# MCU.net
KiCad netlist of a schematic drawn in Altium Designer
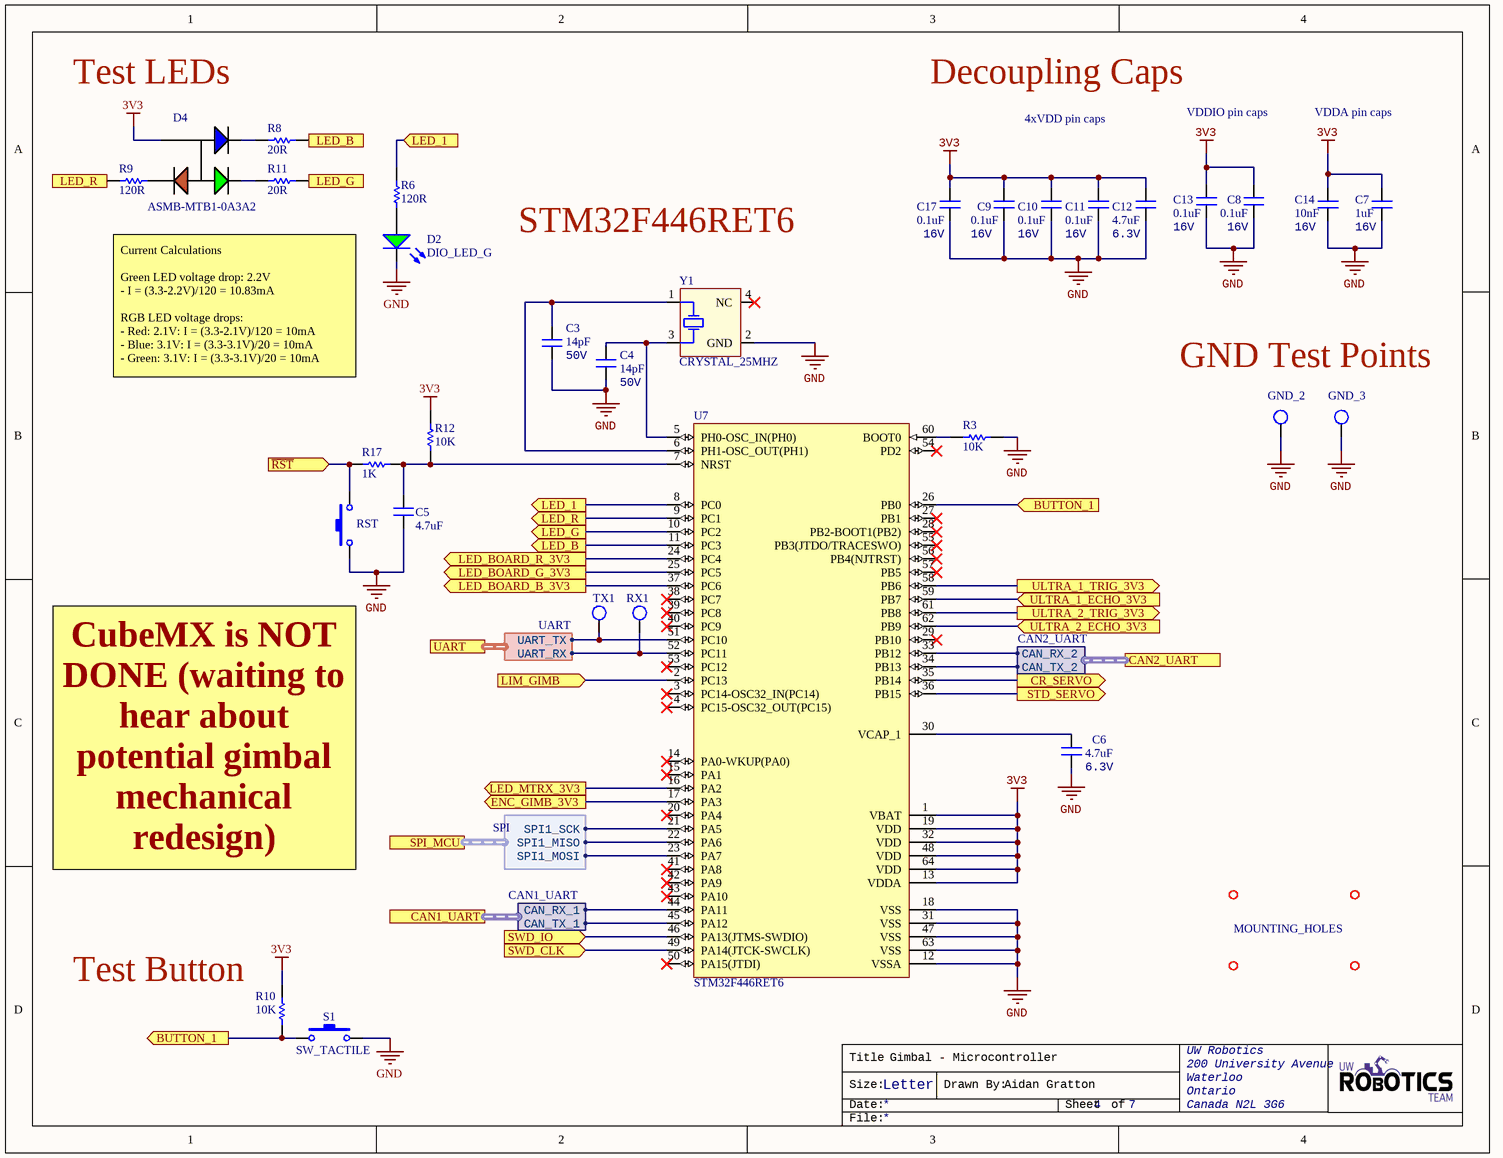
[diagram p0: MCU.SchDoc]

(export (version "E")
  (design (tool "Eeschema 10.0.6"))
  (components
    (comp (ref "C3")
      (value "14pF")
      (footprint "CAPC0603(1608)55_N")
      (description "Cap Ceramic 14pF 50V C0G 5% SMD 0603 125C Cardboard T/R")
      (fields
        (field (name "TOLERANCE") "5%")
        (field (name "VOLTAGE RATING (DC)") "50V")
        (field (name "Comment") "CL10C140JB8NNNC")
      )
      (libsource (lib "UWRT_Schematic_Library_2020") (part "CL10C140JB8NNNC"))
    )
    (comp (ref "C4")
      (value "14pF")
      (footprint "CAPC0603(1608)55_N")
      (description "Cap Ceramic 14pF 50V C0G 5% SMD 0603 125C Cardboard T/R")
      (fields
        (field (name "TOLERANCE") "5%")
        (field (name "VOLTAGE RATING (DC)") "50V")
        (field (name "Comment") "CL10C140JB8NNNC")
      )
      (libsource (lib "UWRT_Schematic_Library_2020") (part "CL10C140JB8NNNC"))
    )
    (comp (ref "C5")
      (value "4.7uF")
      (footprint "CAPC0603(1608)55_N")
      (description "CAP CER 4.7UF 6.3V X5R 0603")
      (fields (field (name "Comment") "CAP_4.7uF_0603"))
      (libsource (lib "UWRT_Schematic_Library_2020") (part "CAP_4.7uF_0603"))
    )
    (comp (ref "C6")
      (value "4.7uF")
      (footprint "CAPC0603(1608)55_N")
      (description "CAP CER 4.7UF 6.3V X5R 0603")
      (fields
        (field (name "MANUFACTURER") "Yageo")
        (field (name "VOLTAGE RATING") "6.3V")
        (field (name "MPN") "CC0603KRX5R5BB475")
      )
      (libsource (lib "UWRT_Schematic_Library_2020") (part "CAP_4.7uF_0603"))
    )
    (comp (ref "C7")
      (value "1uF")
      (footprint "CAPC0603(1608)55_N")
      (description "CAP CER 1UF 16V Y5V 0603")
      (fields
        (field (name "MANUFACTURER") "Yageo")
        (field (name "VOLTAGE RATING") "16V")
        (field (name "MPN") "CC0603ZRY5V7BB105")
      )
      (libsource (lib "UWRT_Schematic_Library_2020") (part "CAP_1uF_16V_0603"))
    )
    (comp (ref "C8")
      (value "0.1uF")
      (footprint "CAPC0603(1608)55_N")
      (description "CAP CER 0.1UF 16V X7R 0603")
      (fields
        (field (name "MANUFACTURER") "Yageo")
        (field (name "VOLTAGE RATING") "16V")
        (field (name "MPN") "CC0603KRX7R7BB104")
      )
      (libsource (lib "UWRT_Schematic_Library_2020") (part "CAP_0.1uF_16V_0603"))
    )
    (comp (ref "C9")
      (value "0.1uF")
      (footprint "CAPC0603(1608)55_N")
      (description "CAP CER 0.1UF 16V X7R 0603")
      (fields
        (field (name "MANUFACTURER") "Yageo")
        (field (name "VOLTAGE RATING") "16V")
        (field (name "MPN") "CC0603KRX7R7BB104")
      )
      (libsource (lib "UWRT_Schematic_Library_2020") (part "CAP_0.1uF_16V_0603"))
    )
    (comp (ref "C10")
      (value "0.1uF")
      (footprint "CAPC0603(1608)55_N")
      (description "CAP CER 0.1UF 16V X7R 0603")
      (fields
        (field (name "MANUFACTURER") "Yageo")
        (field (name "VOLTAGE RATING") "16V")
        (field (name "MPN") "CC0603KRX7R7BB104")
      )
      (libsource (lib "UWRT_Schematic_Library_2020") (part "CAP_0.1uF_16V_0603"))
    )
    (comp (ref "C11")
      (value "0.1uF")
      (footprint "CAPC0603(1608)55_N")
      (description "CAP CER 0.1UF 16V X7R 0603")
      (fields
        (field (name "MANUFACTURER") "Yageo")
        (field (name "VOLTAGE RATING") "16V")
        (field (name "MPN") "CC0603KRX7R7BB104")
      )
      (libsource (lib "UWRT_Schematic_Library_2020") (part "CAP_0.1uF_16V_0603"))
    )
    (comp (ref "C12")
      (value "4.7uF")
      (footprint "CAPC0603(1608)55_N")
      (description "CAP CER 4.7UF 6.3V X5R 0603")
      (fields
        (field (name "MANUFACTURER") "Yageo")
        (field (name "VOLTAGE RATING") "6.3V")
        (field (name "MPN") "CC0603KRX5R5BB475")
      )
      (libsource (lib "UWRT_Schematic_Library_2020") (part "CAP_4.7uF_0603"))
    )
    (comp (ref "C13")
      (value "0.1uF")
      (footprint "CAPC0603(1608)55_N")
      (description "CAP CER 0.1UF 16V X7R 0603")
      (fields
        (field (name "MANUFACTURER") "Yageo")
        (field (name "VOLTAGE RATING") "16V")
        (field (name "MPN") "CC0603KRX7R7BB104")
      )
      (libsource (lib "UWRT_Schematic_Library_2020") (part "CAP_0.1uF_16V_0603"))
    )
    (comp (ref "C14")
      (value "10nF")
      (footprint "CAPC0603(1608)55_N")
      (description "CAP CER 10000PF 16V X7R 0603")
      (fields
        (field (name "MANUFACTURER") "Yageo")
        (field (name "VOLTAGE RATING") "16V")
        (field (name "MPN") "CC0603KRX7R7BB103")
      )
      (libsource (lib "UWRT_Schematic_Library_2020") (part "CAP_10nF_0603"))
    )
    (comp (ref "C17")
      (value "0.1uF")
      (footprint "CAPC0603(1608)55_N")
      (description "CAP CER 0.1UF 16V X7R 0603")
      (fields
        (field (name "MANUFACTURER") "Yageo")
        (field (name "VOLTAGE RATING") "16V")
        (field (name "MPN") "CC0603KRX7R7BB104")
      )
      (libsource (lib "UWRT_Schematic_Library_2020") (part "CAP_0.1uF_16V_0603"))
    )
    (comp (ref "D2")
      (value "DIO_LED_G")
      (footprint "LED_0805_LINE")
      (description "LED GREEN DIFFUSED 0805 SMD")
      (fields (field (name "MANUFACTURER") "OSRAM") (field (name "MPN") "LG R971-KN-1"))
      (libsource (lib "UWRT_Schematic_Library_2020") (part "DIO_LED_G"))
    )
    (comp (ref "D4")
      (value "LED_RGB")
      (footprint "LED_RGB")
      (description "LED RGB DIFFUSED 4PLCC SMD")
      (fields (field (name "MANUFACTURER PART NUMBER 1") "ASMB-MTB1-0A3A2"))
      (libsource (lib "UWRT_Schematic_Library_2020") (part "LED_RGB"))
    )
    (comp (ref "GND_2")
      (value "TESTPOINT_LOOP")
      (footprint "TESTPOINT_LOOP")
      (description "Loop testpoint through-hole pad")
      (fields (field (name "MANUFACTURER") "Keystone Electronics"))
      (libsource (lib "UWRT_Schematic_Library_2020") (part "TESTPOINT_LOOP"))
    )
    (comp (ref "GND_3")
      (value "TESTPOINT_LOOP")
      (footprint "TESTPOINT_LOOP")
      (description "Loop testpoint through-hole pad")
      (fields (field (name "MANUFACTURER") "Keystone Electronics"))
      (libsource (lib "UWRT_Schematic_Library_2020") (part "TESTPOINT_LOOP"))
    )
    (comp (ref "MH1")
      (value "MOUNTING_HOLES")
      (footprint "MOUNTING_HOLE")
      (description "6cm x 6cm")
      (libsource (lib "UWRT_Schematic_Library_2020") (part "MOUNTING_HOLES"))
    )
    (comp (ref "MH2")
      (value "MOUNTING_HOLES")
      (footprint "MOUNTING_HOLE")
      (description "6cm x 6cm")
      (libsource (lib "UWRT_Schematic_Library_2020") (part "MOUNTING_HOLES"))
    )
    (comp (ref "MH3")
      (value "MOUNTING_HOLES")
      (footprint "MOUNTING_HOLE")
      (description "6cm x 6cm")
      (libsource (lib "UWRT_Schematic_Library_2020") (part "MOUNTING_HOLES"))
    )
    (comp (ref "MH4")
      (value "MOUNTING_HOLES")
      (footprint "MOUNTING_HOLE")
      (description "6cm x 6cm")
      (libsource (lib "UWRT_Schematic_Library_2020") (part "MOUNTING_HOLES"))
    )
    (comp (ref "R3")
      (value "10K")
      (footprint "RESC0603(1608)_N")
      (description "RES SMD 10K OHM 5% 1/10W 0603")
      (fields (field (name "MANUFACTURER") "Yageo") (field (name "MPN") "RC0603JR-0710KL"))
      (libsource (lib "UWRT_Schematic_Library_2020") (part "RES_10K_0603"))
    )
    (comp (ref "R6")
      (value "120R")
      (footprint "RESC0603(1608)_N")
      (description "RES SMD 120 OHM 5% 1/10W 0603")
      (fields (field (name "MANUFACTURER") "Yageo") (field (name "MPN") "RC0603JR-07120RL"))
      (libsource (lib "UWRT_Schematic_Library_2020") (part "RES_120R_0603"))
    )
    (comp (ref "R8")
      (value "20R")
      (footprint "RESC0603(1608)_N")
      (description "RES SMD 20 OHM 5% 1/10W 0603")
      (fields (field (name "MANUFACTURER") "Yageo") (field (name "MPN") "RC0603JR-0720RL"))
      (libsource (lib "UWRT_Schematic_Library_2020") (part "RES_20R_0603"))
    )
    (comp (ref "R9")
      (value "120R")
      (footprint "RESC0603(1608)_N")
      (description "RES SMD 120 OHM 5% 1/10W 0603")
      (fields (field (name "MANUFACTURER") "Yageo") (field (name "MPN") "RC0603JR-07120RL"))
      (libsource (lib "UWRT_Schematic_Library_2020") (part "RES_120R_0603"))
    )
    (comp (ref "R10")
      (value "10K")
      (footprint "RESC0603(1608)_N")
      (description "RES SMD 10K OHM 5% 1/10W 0603")
      (fields (field (name "MANUFACTURER") "Yageo") (field (name "TOLERANCE") "5%"))
      (libsource (lib "UWRT_Schematic_Library_2020") (part "RES_10K_0603"))
    )
    (comp (ref "R11")
      (value "20R")
      (footprint "RESC0603(1608)_N")
      (description "RES SMD 20 OHM 5% 1/10W 0603")
      (fields (field (name "MANUFACTURER") "Yageo") (field (name "MPN") "RC0603JR-0720RL"))
      (libsource (lib "UWRT_Schematic_Library_2020") (part "RES_20R_0603"))
    )
    (comp (ref "R12")
      (value "10K")
      (footprint "RESC0603(1608)_N")
      (description "RES SMD 10K OHM 5% 1/10W 0603")
      (fields (field (name "MANUFACTURER") "Yageo") (field (name "MPN") "RC0603JR-0710KL"))
      (libsource (lib "UWRT_Schematic_Library_2020") (part "RES_10K_0603"))
    )
    (comp (ref "R17")
      (value "1K")
      (footprint "RESC0603(1608)_N")
      (description "RES SMD 1K OHM 5% 1/10W 0603")
      (fields (field (name "TOLERANCE") "5%") (field (name "Comment") "RES_1K_0603"))
      (libsource (lib "UWRT_Schematic_Library_2020") (part "RES_1K_0603"))
    )
    (comp (ref "RST")
      (value "SW_PWR")
      (footprint "PTS830GM140")
      (description "Power Switch (Red)")
      (fields (field (name "MPN") "PTS830GM140 SMTR LFS") (field (name "MANUFACTURER") "C&K"))
      (libsource (lib "UWRT_Schematic_Library_2020") (part "SW_PWR"))
    )
    (comp (ref "RX1")
      (value "TESTPOINT_LOOP")
      (footprint "TESTPOINT_LOOP")
      (description "Loop testpoint through-hole pad")
      (fields (field (name "MANUFACTURER") "Keystone Electronics"))
      (libsource (lib "UWRT_Schematic_Library_2020") (part "TESTPOINT_LOOP"))
    )
    (comp (ref "S1")
      (value "SW_TACTILE")
      (footprint "B3U-1100P")
      (description "Tactile Switch (Grey)")
      (fields (field (name "MPN") "B3U-1100P") (field (name "MANUFACTURER") "Omron Electronics Inc-EMC Div"))
      (libsource (lib "UWRT_Schematic_Library_2020") (part "SW_TACTILE"))
    )
    (comp (ref "TX1")
      (value "TESTPOINT_LOOP")
      (footprint "TESTPOINT_LOOP")
      (description "Loop testpoint through-hole pad")
      (fields (field (name "MANUFACTURER") "Keystone Electronics"))
      (libsource (lib "UWRT_Schematic_Library_2020") (part "TESTPOINT_LOOP"))
    )
    (comp (ref "U7")
      (value "STM32F446RET6")
      (footprint "STM-LQFP64_L")
      (libsource (lib "UWRT_Schematic_Library_2020") (part "MCU_STM32F446RET6"))
    )
    (comp (ref "Y1")
      (value "CRYSTAL_25MHZ")
      (footprint "AVX-CX2520DB32000D0GEJZ1-4_V")
      (description "CRYSTAL 25.0000MHZ 12PF SMD")
      (libsource (lib "UWRT_Schematic_Library_2020") (part "CRYSTAL_25MHZ"))
    )
  )
  (nets
    (net (code "5") (name "/BUTTON_1") (class "Default")
      (node (ref "R10") (pin "2") (pinfunction "2_2") (pintype "passive"))
      (node (ref "S1") (pin "1") (pinfunction "1_1") (pintype "passive"))
      (node (ref "U7") (pin "26") (pinfunction "PB0_26") (pintype "bidirectional"))
    )
    (net (code "6") (name "/CAN_RX_1") (class "Default")
      (node (ref "U7") (pin "44") (pinfunction "PA11_44") (pintype "bidirectional"))
    )
    (net (code "7") (name "/CAN_RX_2") (class "Default")
      (node (ref "U7") (pin "33") (pinfunction "PB12_33") (pintype "bidirectional"))
    )
    (net (code "8") (name "/CAN_TX_1") (class "Default")
      (node (ref "U7") (pin "45") (pinfunction "PA12_45") (pintype "bidirectional"))
    )
    (net (code "9") (name "/CAN_TX_2") (class "Default")
      (node (ref "U7") (pin "34") (pinfunction "PB13_34") (pintype "bidirectional"))
    )
    (net (code "10") (name "/CR_SERVO") (class "Default")
      (node (ref "U7") (pin "35") (pinfunction "PB14_35") (pintype "bidirectional"))
    )
    (net (code "11") (name "/ENC_GIMB_3V3") (class "Default")
      (node (ref "U7") (pin "17") (pinfunction "PA3_17") (pintype "bidirectional"))
    )
    (net (code "12") (name "/LED_1") (class "Default")
      (node (ref "R6") (pin "1") (pinfunction "1_1") (pintype "passive"))
      (node (ref "U7") (pin "8") (pinfunction "PC0_8") (pintype "bidirectional"))
    )
    (net (code "13") (name "/LED_B") (class "Default")
      (node (ref "R8") (pin "2") (pinfunction "2_2") (pintype "passive"))
      (node (ref "U7") (pin "11") (pinfunction "PC3_11") (pintype "bidirectional"))
    )
    (net (code "14") (name "/LED_BOARD_B_3V3") (class "Default")
      (node (ref "U7") (pin "37") (pinfunction "PC6_37") (pintype "bidirectional"))
    )
    (net (code "15") (name "/LED_BOARD_G_3V3") (class "Default")
      (node (ref "U7") (pin "25") (pinfunction "PC5_25") (pintype "bidirectional"))
    )
    (net (code "16") (name "/LED_BOARD_R_3V3") (class "Default")
      (node (ref "U7") (pin "24") (pinfunction "PC4_24") (pintype "bidirectional"))
    )
    (net (code "17") (name "/LED_G") (class "Default")
      (node (ref "R11") (pin "2") (pinfunction "2_2") (pintype "passive"))
      (node (ref "U7") (pin "10") (pinfunction "PC2_10") (pintype "bidirectional"))
    )
    (net (code "18") (name "/LED_MTRX_3V3") (class "Default")
      (node (ref "U7") (pin "16") (pinfunction "PA2_16") (pintype "bidirectional"))
    )
    (net (code "19") (name "/LED_R") (class "Default")
      (node (ref "R9") (pin "1") (pinfunction "1_1") (pintype "passive"))
      (node (ref "U7") (pin "9") (pinfunction "PC1_9") (pintype "bidirectional"))
    )
    (net (code "20") (name "/LIM_GIMB") (class "Default")
      (node (ref "U7") (pin "2") (pinfunction "PC13_2") (pintype "bidirectional"))
    )
    (net (code "21") (name "/SPI1_MISO") (class "Default")
      (node (ref "U7") (pin "22") (pinfunction "PA6_22") (pintype "bidirectional"))
    )
    (net (code "22") (name "/SPI1_MOSI") (class "Default")
      (node (ref "U7") (pin "23") (pinfunction "PA7_23") (pintype "bidirectional"))
    )
    (net (code "23") (name "/SPI1_SCK") (class "Default")
      (node (ref "U7") (pin "21") (pinfunction "PA5_21") (pintype "bidirectional"))
    )
    (net (code "24") (name "/STD_SERVO") (class "Default")
      (node (ref "U7") (pin "36") (pinfunction "PB15_36") (pintype "bidirectional"))
    )
    (net (code "25") (name "/SWD_CLK") (class "Default")
      (node (ref "U7") (pin "49") (pinfunction "PA14(JTCK-SWCLK)_49") (pintype "bidirectional"))
    )
    (net (code "26") (name "/SWD_IO") (class "Default")
      (node (ref "U7") (pin "46") (pinfunction "PA13(JTMS-SWDIO)_46") (pintype "bidirectional"))
    )
    (net (code "27") (name "/UART_RX") (class "Default")
      (node (ref "RX1") (pin "1") (pintype "passive"))
      (node (ref "U7") (pin "52") (pinfunction "PC11_52") (pintype "bidirectional"))
    )
    (net (code "28") (name "/UART_TX") (class "Default")
      (node (ref "TX1") (pin "1") (pintype "passive"))
      (node (ref "U7") (pin "51") (pinfunction "PC10_51") (pintype "bidirectional"))
    )
    (net (code "29") (name "/ULTRA_1_ECHO_3V3") (class "Default")
      (node (ref "U7") (pin "59") (pinfunction "PB7_59") (pintype "bidirectional"))
    )
    (net (code "30") (name "/ULTRA_1_TRIG_3V3") (class "Default")
      (node (ref "U7") (pin "58") (pinfunction "PB6_58") (pintype "bidirectional"))
    )
    (net (code "31") (name "/ULTRA_2_ECHO_3V3") (class "Default")
      (node (ref "U7") (pin "62") (pinfunction "PB9_62") (pintype "bidirectional"))
    )
    (net (code "32") (name "/ULTRA_2_TRIG_3V3") (class "Default")
      (node (ref "U7") (pin "61") (pinfunction "PB8_61") (pintype "bidirectional"))
    )
    (net (code "37") (name "/~{RST}") (class "Default")
      (node (ref "R17") (pin "1") (pinfunction "1_1") (pintype "passive"))
      (node (ref "RST") (pin "2") (pinfunction "2_2") (pintype "passive"))
    )
    (net (code "38") (name "3V3") (class "Default")
      (node (ref "C10") (pin "2") (pinfunction "2_2") (pintype "passive"))
      (node (ref "C11") (pin "2") (pinfunction "2_2") (pintype "passive"))
      (node (ref "C12") (pin "2") (pinfunction "2_2") (pintype "passive"))
      (node (ref "C13") (pin "2") (pinfunction "2_2") (pintype "passive"))
      (node (ref "C14") (pin "2") (pinfunction "2_2") (pintype "passive"))
      (node (ref "C17") (pin "2") (pinfunction "2_2") (pintype "passive"))
      (node (ref "C7") (pin "2") (pinfunction "2_2") (pintype "passive"))
      (node (ref "C8") (pin "2") (pinfunction "2_2") (pintype "passive"))
      (node (ref "C9") (pin "2") (pinfunction "2_2") (pintype "passive"))
      (node (ref "D4") (pin "4") (pinfunction "9_4") (pintype "passive"))
      (node (ref "R10") (pin "1") (pinfunction "1_1") (pintype "passive"))
      (node (ref "R12") (pin "2") (pinfunction "2_2") (pintype "passive"))
      (node (ref "U7") (pin "1") (pinfunction "VBAT_1") (pintype "power_in"))
      (node (ref "U7") (pin "13") (pinfunction "VDDA_13") (pintype "power_in"))
      (node (ref "U7") (pin "19") (pinfunction "VDD_19") (pintype "power_in"))
      (node (ref "U7") (pin "32") (pinfunction "VDD_32") (pintype "power_in"))
      (node (ref "U7") (pin "48") (pinfunction "VDD_48") (pintype "power_in"))
      (node (ref "U7") (pin "64") (pinfunction "VDD_64") (pintype "power_in"))
    )
    (net (code "39") (name "GND") (class "Default")
      (node (ref "C10") (pin "1") (pinfunction "1_1") (pintype "passive"))
      (node (ref "C11") (pin "1") (pinfunction "1_1") (pintype "passive"))
      (node (ref "C12") (pin "1") (pinfunction "1_1") (pintype "passive"))
      (node (ref "C13") (pin "1") (pinfunction "1_1") (pintype "passive"))
      (node (ref "C14") (pin "1") (pinfunction "1_1") (pintype "passive"))
      (node (ref "C17") (pin "1") (pinfunction "1_1") (pintype "passive"))
      (node (ref "C3") (pin "1") (pinfunction "1_1") (pintype "passive"))
      (node (ref "C4") (pin "1") (pinfunction "1_1") (pintype "passive"))
      (node (ref "C5") (pin "1") (pinfunction "1_1") (pintype "passive"))
      (node (ref "C6") (pin "1") (pinfunction "1_1") (pintype "passive"))
      (node (ref "C7") (pin "1") (pinfunction "1_1") (pintype "passive"))
      (node (ref "C8") (pin "1") (pinfunction "1_1") (pintype "passive"))
      (node (ref "C9") (pin "1") (pinfunction "1_1") (pintype "passive"))
      (node (ref "D2") (pin "2") (pinfunction "K_2") (pintype "passive"))
      (node (ref "GND_2") (pin "1") (pintype "passive"))
      (node (ref "GND_3") (pin "1") (pintype "passive"))
      (node (ref "R3") (pin "2") (pinfunction "2_2") (pintype "passive"))
      (node (ref "RST") (pin "1") (pinfunction "1_1") (pintype "passive"))
      (node (ref "S1") (pin "2") (pinfunction "2_2") (pintype "passive"))
      (node (ref "U7") (pin "12") (pinfunction "VSSA_12") (pintype "power_in"))
      (node (ref "U7") (pin "18") (pinfunction "VSS_18") (pintype "power_in"))
      (node (ref "U7") (pin "31") (pinfunction "VSS_31") (pintype "power_in"))
      (node (ref "U7") (pin "47") (pinfunction "VSS_47") (pintype "power_in"))
      (node (ref "U7") (pin "63") (pinfunction "VSS_63") (pintype "power_in"))
      (node (ref "Y1") (pin "2") (pinfunction "GND_2") (pintype "power_in"))
    )
    (net (code "40") (name "Net-(D2-A)") (class "Default")
      (node (ref "D2") (pin "1") (pinfunction "A_1") (pintype "passive"))
      (node (ref "R6") (pin "2") (pinfunction "2_2") (pintype "passive"))
    )
    (net (code "41") (name "Net-(D4-10)") (class "Default")
      (node (ref "D4") (pin "3") (pinfunction "10_3") (pintype "passive"))
      (node (ref "R8") (pin "1") (pinfunction "1_1") (pintype "passive"))
    )
    (net (code "42") (name "Net-(D4-11)") (class "Default")
      (node (ref "D4") (pin "1") (pinfunction "11_1") (pintype "passive"))
      (node (ref "R9") (pin "2") (pinfunction "2_2") (pintype "passive"))
    )
    (net (code "43") (name "Net-(D4-12)") (class "Default")
      (node (ref "D4") (pin "2") (pinfunction "12_2") (pintype "passive"))
      (node (ref "R11") (pin "1") (pinfunction "1_1") (pintype "passive"))
    )
    (net (code "44") (name "Net-(U7-BOOT0)") (class "Default")
      (node (ref "R3") (pin "1") (pinfunction "1_1") (pintype "passive"))
      (node (ref "U7") (pin "60") (pinfunction "BOOT0_60") (pintype "input"))
    )
    (net (code "45") (name "Net-(U7-NRST)") (class "Default")
      (node (ref "C5") (pin "2") (pinfunction "2_2") (pintype "passive"))
      (node (ref "R12") (pin "1") (pinfunction "1_1") (pintype "passive"))
      (node (ref "R17") (pin "2") (pinfunction "2_2") (pintype "passive"))
      (node (ref "U7") (pin "7") (pinfunction "NRST_7") (pintype "bidirectional"))
    )
    (net (code "46") (name "Net-(U7-PH0-OSC_IN(PH0))") (class "Default")
      (node (ref "C4") (pin "2") (pinfunction "2_2") (pintype "passive"))
      (node (ref "U7") (pin "5") (pinfunction "PH0-OSC_IN(PH0)_5") (pintype "bidirectional"))
      (node (ref "Y1") (pin "3") (pinfunction "HOT_3") (pintype "passive"))
    )
    (net (code "47") (name "Net-(U7-PH1-OSC_OUT(PH1))") (class "Default")
      (node (ref "C3") (pin "2") (pinfunction "2_2") (pintype "passive"))
      (node (ref "U7") (pin "6") (pinfunction "PH1-OSC_OUT(PH1)_6") (pintype "bidirectional"))
      (node (ref "Y1") (pin "1") (pinfunction "HOT_1") (pintype "passive"))
    )
    (net (code "48") (name "Net-(U7-VCAP_1)") (class "Default")
      (node (ref "C6") (pin "2") (pinfunction "2_2") (pintype "passive"))
      (node (ref "U7") (pin "30") (pinfunction "VCAP_1_30") (pintype "passive"))
    )
    (net (code "49") (name "unconnected-(U7-PA0-WKUP(PA0)-Pad14)") (class "Default")
      (node (ref "U7") (pin "14") (pinfunction "PA0-WKUP(PA0)_14") (pintype "bidirectional+no_connect"))
    )
    (net (code "50") (name "unconnected-(U7-PA1-Pad15)") (class "Default")
      (node (ref "U7") (pin "15") (pinfunction "PA1_15") (pintype "bidirectional+no_connect"))
    )
    (net (code "51") (name "unconnected-(U7-PA4-Pad20)") (class "Default")
      (node (ref "U7") (pin "20") (pinfunction "PA4_20") (pintype "bidirectional+no_connect"))
    )
    (net (code "52") (name "unconnected-(U7-PA8-Pad41)") (class "Default")
      (node (ref "U7") (pin "41") (pinfunction "PA8_41") (pintype "bidirectional+no_connect"))
    )
    (net (code "53") (name "unconnected-(U7-PA9-Pad42)") (class "Default")
      (node (ref "U7") (pin "42") (pinfunction "PA9_42") (pintype "bidirectional+no_connect"))
    )
    (net (code "54") (name "unconnected-(U7-PA10-Pad43)") (class "Default")
      (node (ref "U7") (pin "43") (pinfunction "PA10_43") (pintype "bidirectional+no_connect"))
    )
    (net (code "55") (name "unconnected-(U7-PA15(JTDI)-Pad50)") (class "Default")
      (node (ref "U7") (pin "50") (pinfunction "PA15(JTDI)_50") (pintype "bidirectional+no_connect"))
    )
    (net (code "56") (name "unconnected-(U7-PB1-Pad27)") (class "Default")
      (node (ref "U7") (pin "27") (pinfunction "PB1_27") (pintype "bidirectional+no_connect"))
    )
    (net (code "57") (name "unconnected-(U7-PB2-BOOT1(PB2)-Pad28)") (class "Default")
      (node (ref "U7") (pin "28") (pinfunction "PB2-BOOT1(PB2)_28") (pintype "bidirectional+no_connect"))
    )
    (net (code "58") (name "unconnected-(U7-PB3(JTDO{slash}TRACESWO)-Pad55)") (class "Default")
      (node (ref "U7") (pin "55") (pinfunction "PB3(JTDO/TRACESWO)_55") (pintype "bidirectional+no_connect"))
    )
    (net (code "59") (name "unconnected-(U7-PB4(NJTRST)-Pad56)") (class "Default")
      (node (ref "U7") (pin "56") (pinfunction "PB4(NJTRST)_56") (pintype "bidirectional+no_connect"))
    )
    (net (code "60") (name "unconnected-(U7-PB5-Pad57)") (class "Default")
      (node (ref "U7") (pin "57") (pinfunction "PB5_57") (pintype "bidirectional+no_connect"))
    )
    (net (code "61") (name "unconnected-(U7-PB10-Pad29)") (class "Default")
      (node (ref "U7") (pin "29") (pinfunction "PB10_29") (pintype "bidirectional+no_connect"))
    )
    (net (code "62") (name "unconnected-(U7-PC7-Pad38)") (class "Default")
      (node (ref "U7") (pin "38") (pinfunction "PC7_38") (pintype "bidirectional+no_connect"))
    )
    (net (code "63") (name "unconnected-(U7-PC8-Pad39)") (class "Default")
      (node (ref "U7") (pin "39") (pinfunction "PC8_39") (pintype "bidirectional+no_connect"))
    )
    (net (code "64") (name "unconnected-(U7-PC9-Pad40)") (class "Default")
      (node (ref "U7") (pin "40") (pinfunction "PC9_40") (pintype "bidirectional+no_connect"))
    )
    (net (code "65") (name "unconnected-(U7-PC12-Pad53)") (class "Default")
      (node (ref "U7") (pin "53") (pinfunction "PC12_53") (pintype "bidirectional+no_connect"))
    )
    (net (code "66") (name "unconnected-(U7-PC14-OSC32_IN(PC14)-Pad3)") (class "Default")
      (node (ref "U7") (pin "3") (pinfunction "PC14-OSC32_IN(PC14)_3") (pintype "bidirectional+no_connect"))
    )
    (net (code "67") (name "unconnected-(U7-PC15-OSC32_OUT(PC15)-Pad4)") (class "Default")
      (node (ref "U7") (pin "4") (pinfunction "PC15-OSC32_OUT(PC15)_4") (pintype "bidirectional+no_connect"))
    )
    (net (code "68") (name "unconnected-(U7-PD2-Pad54)") (class "Default")
      (node (ref "U7") (pin "54") (pinfunction "PD2_54") (pintype "bidirectional+no_connect"))
    )
    (net (code "69") (name "unconnected-(Y1-NC-Pad4)") (class "Default")
      (node (ref "Y1") (pin "4") (pinfunction "NC_4") (pintype "passive+no_connect"))
    )
  )
)
